# Sheet1.net
KiCad netlist of a schematic drawn in Altium Designer
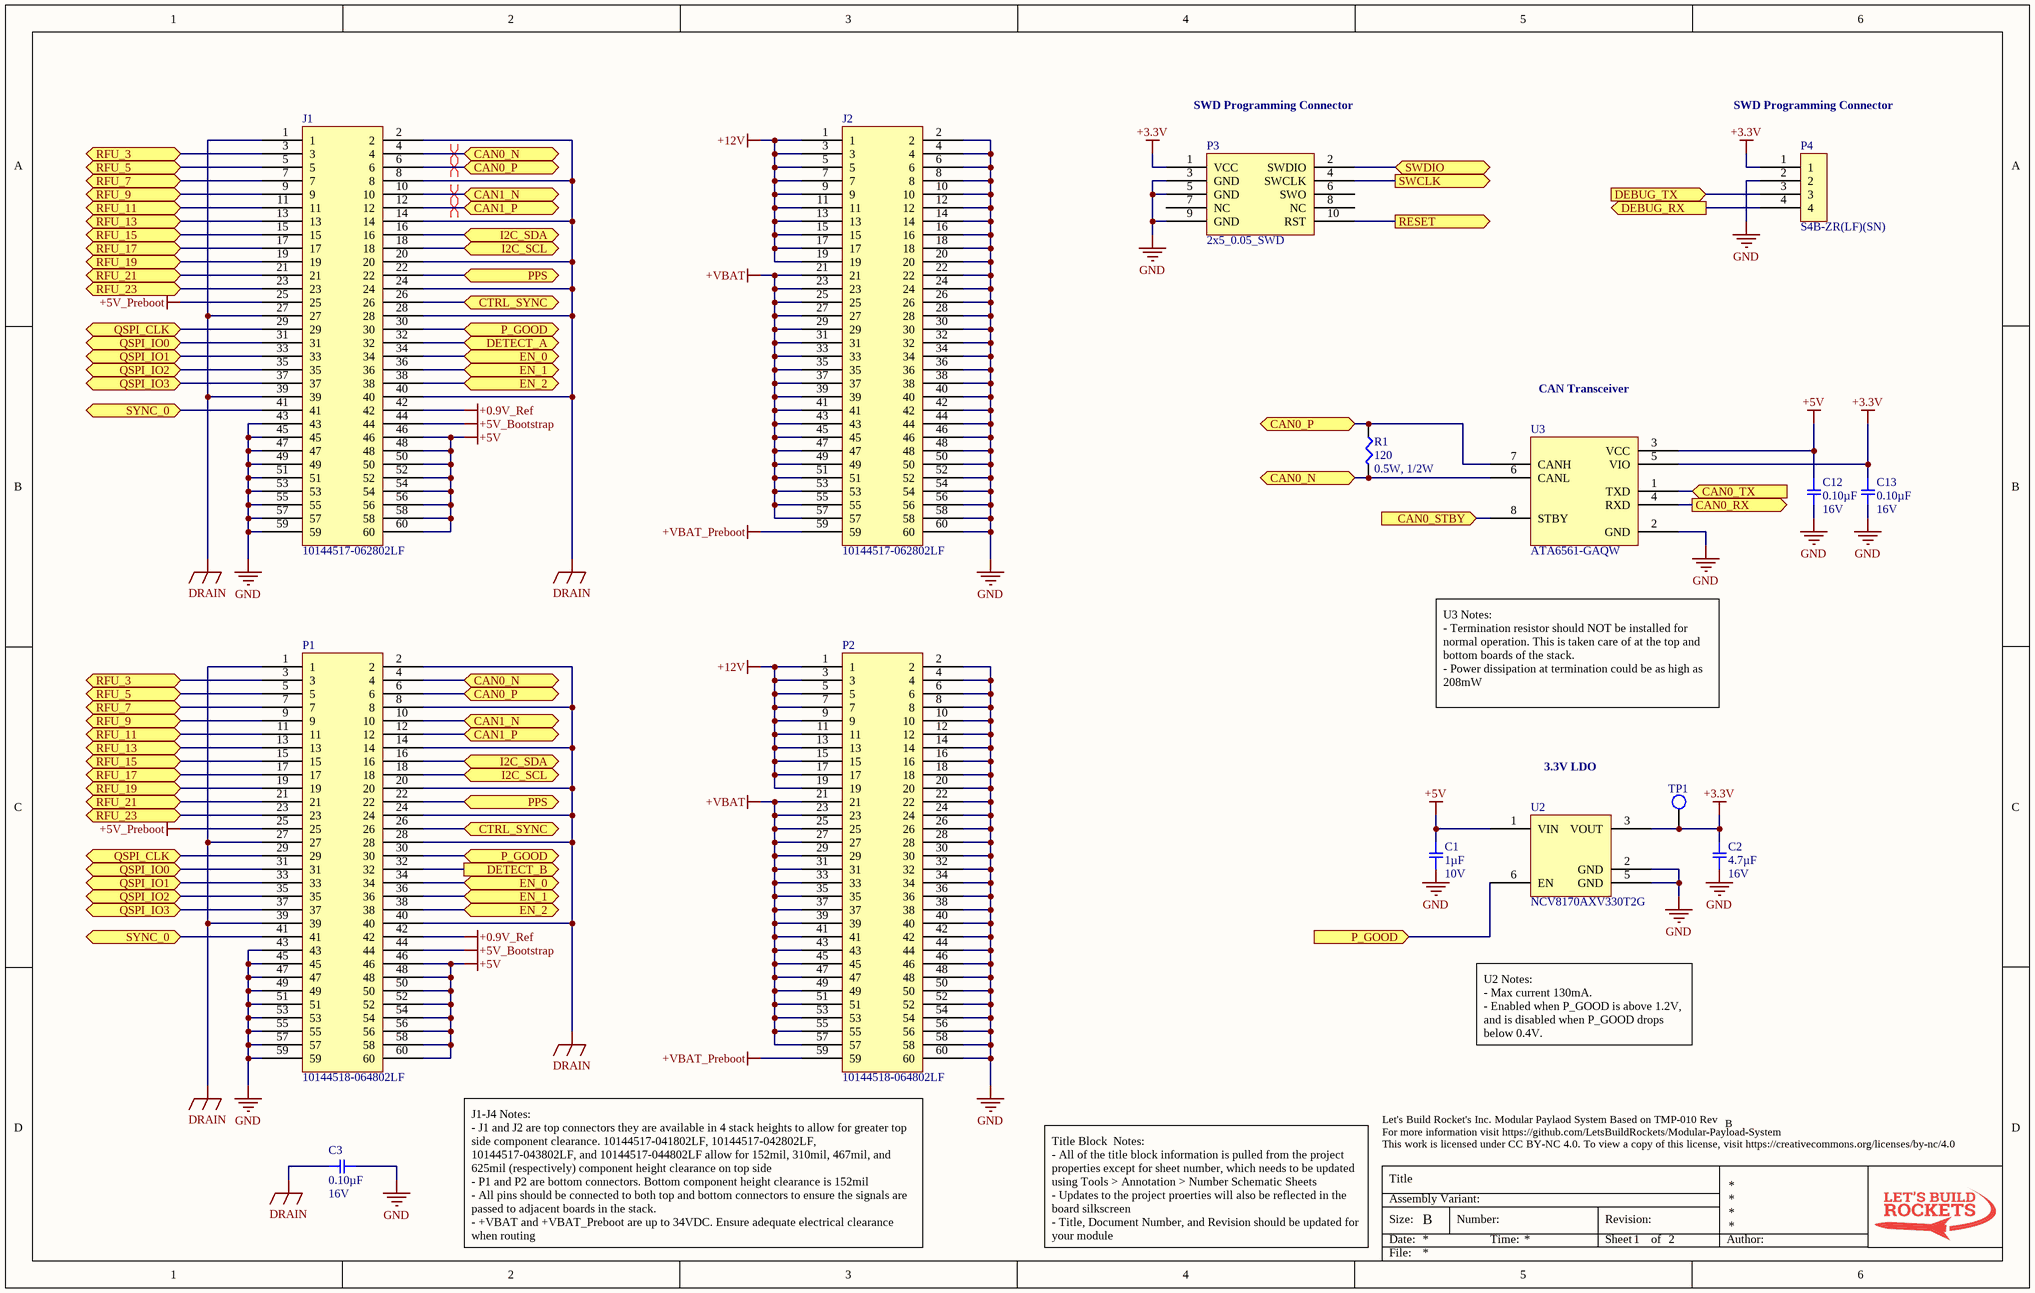
[diagram p0: Sheet1.SchDoc]

(export (version "E")
  (design (tool "Eeschema 10.0.6"))
  (components
    (comp (ref "C1")
      (value "1µF")
      (footprint "SMD-0402C")
      (description "CAP CER 1UF 10V X7S 0402")
      (fields
        (field (name "DIGI-KEY PART NUMBER") "490-13409-1-ND")
        (field (name "PART NUMBER") "GCM155C71A105KE38D")
        (field (name "VOLTAGE") "10V")
      )
      (libsource (lib "capacitor_murata_0402") (part "GCM155C71A105KE38D"))
    )
    (comp (ref "C2")
      (value "4.7µF")
      (footprint "SMD-0805C")
      (description "CAP CER 4.7UF 16V X7R 0805")
      (fields
        (field (name "DIGI-KEY PART NUMBER") "490-10557-1-ND")
        (field (name "PART NUMBER") "GCJ21BR71C475KA01L")
        (field (name "VOLTAGE") "16V")
      )
      (libsource (lib "capacitor_murata_0805") (part "GCJ21BR71C475KA01L"))
    )
    (comp (ref "C3")
      (value "0.10µF")
      (footprint "SMD-0402C")
      (description "CAP CER 0.1UF 16V X7R 0402")
      (fields
        (field (name "DIGI-KEY PART NUMBER") "490-4759-1-ND")
        (field (name "PART NUMBER") "GCM155R71C104KA55D")
        (field (name "VOLTAGE") "16V")
      )
      (libsource (lib "capacitor_murata_0402") (part "GCM155R71C104KA55D"))
    )
    (comp (ref "C12")
      (value "0.10µF")
      (footprint "SMD-0402C")
      (description "CAP CER 0.1UF 16V X7R 0402")
      (fields
        (field (name "DIGI-KEY PART NUMBER") "490-4759-1-ND")
        (field (name "PART NUMBER") "GCM155R71C104KA55D")
        (field (name "VOLTAGE") "16V")
      )
      (libsource (lib "capacitor_murata_0402") (part "GCM155R71C104KA55D"))
    )
    (comp (ref "C13")
      (value "0.10µF")
      (footprint "SMD-0402C")
      (description "CAP CER 0.1UF 16V X7R 0402")
      (fields
        (field (name "DIGI-KEY PART NUMBER") "490-4759-1-ND")
        (field (name "PART NUMBER") "GCM155R71C104KA55D")
        (field (name "VOLTAGE") "16V")
      )
      (libsource (lib "capacitor_murata_0402") (part "GCM155R71C104KA55D"))
    )
    (comp (ref "J1")
      (value "10144517-062802LF")
      (footprint "10144517-062802LF")
      (libsource (lib "ModularPayload") (part "10144517-062802LF"))
    )
    (comp (ref "J2")
      (value "10144517-062802LF")
      (footprint "10144517-062802LF")
      (libsource (lib "ModularPayload") (part "10144517-062802LF"))
    )
    (comp (ref "P1")
      (value "10144518-064802LF")
      (footprint "10144518-064802LF")
      (libsource (lib "ModularPayload") (part "10144518-064802LF"))
    )
    (comp (ref "P2")
      (value "10144518-064802LF")
      (footprint "10144518-064802LF")
      (libsource (lib "ModularPayload") (part "10144518-064802LF"))
    )
    (comp (ref "P3")
      (value "2x5_0.05_SWD")
      (footprint "2x5_0.05_R")
      (libsource (lib "ModularPayload") (part "2x5_0.05_SWD"))
    )
    (comp (ref "P4")
      (value "S4B-ZR(LF)(SN)")
      (footprint "S4B-ZR(LF)(SN)")
      (libsource (lib "ModularPayload") (part "S4B-ZR(LF)(SN)"))
    )
    (comp (ref "R1")
      (value "120")
      (footprint "SMD-0805-RES")
      (description "RES SMD 120 OHM 5% 1/2W 0805")
      (fields
        (field (name "PART NUMBER") "ERJ-P6WJ121V")
        (field (name "DIGI-KEY PART NUMBER") "P16943CT-ND")
        (field (name "POWER (WATTS)") "0.5W, 1/2W")
      )
      (libsource (lib "Panasonic_ERJ_0805") (part "ERJ-P6WJ121V"))
    )
    (comp (ref "TP1") (value "TP") (footprint "TP_SMD_40") (libsource (lib "TP") (part "TP")))
    (comp (ref "U2")
      (value "NCV8170AXV330T2G")
      (footprint "SOTFL50P160X60-6N")
      (libsource (lib "ModularPayload") (part "NCV8170AXV330T2G"))
    )
    (comp (ref "U3")
      (value "ATA6561-GAQW")
      (footprint "SOIC127P600X175-8N")
      (libsource (lib "ModularPayload") (part "ATA6561-GAQW"))
    )
  )
  (nets
    (net (code "1") (name "+0.9V_Ref") (class "Default")
      (node (ref "J1") (pin "42") (pinfunction "42_42") (pintype "passive"))
      (node (ref "P1") (pin "42") (pinfunction "42_42") (pintype "passive"))
    )
    (net (code "2") (name "+3.3V") (class "Default")
      (node (ref "C13") (pin "1") (pinfunction "1_1") (pintype "passive"))
      (node (ref "C2") (pin "2") (pinfunction "2_2") (pintype "passive"))
      (node (ref "P3") (pin "1") (pinfunction "VCC_1") (pintype "passive"))
      (node (ref "P4") (pin "1") (pinfunction "1_1") (pintype "passive"))
      (node (ref "TP1") (pin "1") (pintype "passive"))
      (node (ref "U2") (pin "3") (pinfunction "VOUT_3") (pintype "passive"))
      (node (ref "U3") (pin "5") (pinfunction "VIO_5") (pintype "passive"))
    )
    (net (code "3") (name "+5V") (class "Default")
      (node (ref "C1") (pin "2") (pinfunction "2_2") (pintype "passive"))
      (node (ref "C12") (pin "1") (pinfunction "1_1") (pintype "passive"))
      (node (ref "J1") (pin "46") (pinfunction "46_46") (pintype "passive"))
      (node (ref "J1") (pin "48") (pinfunction "48_48") (pintype "passive"))
      (node (ref "J1") (pin "50") (pinfunction "50_50") (pintype "passive"))
      (node (ref "J1") (pin "52") (pinfunction "52_52") (pintype "passive"))
      (node (ref "J1") (pin "54") (pinfunction "54_54") (pintype "passive"))
      (node (ref "J1") (pin "56") (pinfunction "56_56") (pintype "passive"))
      (node (ref "J1") (pin "58") (pinfunction "58_58") (pintype "passive"))
      (node (ref "J1") (pin "60") (pinfunction "60_60") (pintype "passive"))
      (node (ref "P1") (pin "46") (pinfunction "46_46") (pintype "passive"))
      (node (ref "P1") (pin "48") (pinfunction "48_48") (pintype "passive"))
      (node (ref "P1") (pin "50") (pinfunction "50_50") (pintype "passive"))
      (node (ref "P1") (pin "52") (pinfunction "52_52") (pintype "passive"))
      (node (ref "P1") (pin "54") (pinfunction "54_54") (pintype "passive"))
      (node (ref "P1") (pin "56") (pinfunction "56_56") (pintype "passive"))
      (node (ref "P1") (pin "58") (pinfunction "58_58") (pintype "passive"))
      (node (ref "P1") (pin "60") (pinfunction "60_60") (pintype "passive"))
      (node (ref "U2") (pin "1") (pinfunction "VIN_1") (pintype "passive"))
      (node (ref "U3") (pin "3") (pinfunction "VCC_3") (pintype "passive"))
    )
    (net (code "4") (name "+5V_Bootstrap") (class "Default")
      (node (ref "J1") (pin "44") (pinfunction "44_44") (pintype "passive"))
      (node (ref "P1") (pin "44") (pinfunction "44_44") (pintype "passive"))
    )
    (net (code "5") (name "+5V_Preboot") (class "Default")
      (node (ref "J1") (pin "25") (pinfunction "25_25") (pintype "passive"))
      (node (ref "P1") (pin "25") (pinfunction "25_25") (pintype "passive"))
    )
    (net (code "6") (name "+12V") (class "Default")
      (node (ref "J2") (pin "1") (pinfunction "1_1") (pintype "passive"))
      (node (ref "J2") (pin "11") (pinfunction "11_11") (pintype "passive"))
      (node (ref "J2") (pin "13") (pinfunction "13_13") (pintype "passive"))
      (node (ref "J2") (pin "15") (pinfunction "15_15") (pintype "passive"))
      (node (ref "J2") (pin "17") (pinfunction "17_17") (pintype "passive"))
      (node (ref "J2") (pin "19") (pinfunction "19_19") (pintype "passive"))
      (node (ref "J2") (pin "3") (pinfunction "3_3") (pintype "passive"))
      (node (ref "J2") (pin "5") (pinfunction "5_5") (pintype "passive"))
      (node (ref "J2") (pin "7") (pinfunction "7_7") (pintype "passive"))
      (node (ref "J2") (pin "9") (pinfunction "9_9") (pintype "passive"))
      (node (ref "P2") (pin "1") (pinfunction "1_1") (pintype "passive"))
      (node (ref "P2") (pin "11") (pinfunction "11_11") (pintype "passive"))
      (node (ref "P2") (pin "13") (pinfunction "13_13") (pintype "passive"))
      (node (ref "P2") (pin "15") (pinfunction "15_15") (pintype "passive"))
      (node (ref "P2") (pin "17") (pinfunction "17_17") (pintype "passive"))
      (node (ref "P2") (pin "19") (pinfunction "19_19") (pintype "passive"))
      (node (ref "P2") (pin "3") (pinfunction "3_3") (pintype "passive"))
      (node (ref "P2") (pin "5") (pinfunction "5_5") (pintype "passive"))
      (node (ref "P2") (pin "7") (pinfunction "7_7") (pintype "passive"))
      (node (ref "P2") (pin "9") (pinfunction "9_9") (pintype "passive"))
    )
    (net (code "7") (name "+VBAT") (class "Default")
      (node (ref "J2") (pin "21") (pinfunction "21_21") (pintype "passive"))
      (node (ref "J2") (pin "23") (pinfunction "23_23") (pintype "passive"))
      (node (ref "J2") (pin "25") (pinfunction "25_25") (pintype "passive"))
      (node (ref "J2") (pin "27") (pinfunction "27_27") (pintype "passive"))
      (node (ref "J2") (pin "29") (pinfunction "29_29") (pintype "passive"))
      (node (ref "J2") (pin "31") (pinfunction "31_31") (pintype "passive"))
      (node (ref "J2") (pin "33") (pinfunction "33_33") (pintype "passive"))
      (node (ref "J2") (pin "35") (pinfunction "35_35") (pintype "passive"))
      (node (ref "J2") (pin "37") (pinfunction "37_37") (pintype "passive"))
      (node (ref "J2") (pin "39") (pinfunction "39_39") (pintype "passive"))
      (node (ref "J2") (pin "41") (pinfunction "41_41") (pintype "passive"))
      (node (ref "J2") (pin "43") (pinfunction "43_43") (pintype "passive"))
      (node (ref "J2") (pin "45") (pinfunction "45_45") (pintype "passive"))
      (node (ref "J2") (pin "47") (pinfunction "47_47") (pintype "passive"))
      (node (ref "J2") (pin "49") (pinfunction "49_49") (pintype "passive"))
      (node (ref "J2") (pin "51") (pinfunction "51_51") (pintype "passive"))
      (node (ref "J2") (pin "53") (pinfunction "53_53") (pintype "passive"))
      (node (ref "J2") (pin "55") (pinfunction "55_55") (pintype "passive"))
      (node (ref "J2") (pin "57") (pinfunction "57_57") (pintype "passive"))
      (node (ref "P2") (pin "21") (pinfunction "21_21") (pintype "passive"))
      (node (ref "P2") (pin "23") (pinfunction "23_23") (pintype "passive"))
      (node (ref "P2") (pin "25") (pinfunction "25_25") (pintype "passive"))
      (node (ref "P2") (pin "27") (pinfunction "27_27") (pintype "passive"))
      (node (ref "P2") (pin "29") (pinfunction "29_29") (pintype "passive"))
      (node (ref "P2") (pin "31") (pinfunction "31_31") (pintype "passive"))
      (node (ref "P2") (pin "33") (pinfunction "33_33") (pintype "passive"))
      (node (ref "P2") (pin "35") (pinfunction "35_35") (pintype "passive"))
      (node (ref "P2") (pin "37") (pinfunction "37_37") (pintype "passive"))
      (node (ref "P2") (pin "39") (pinfunction "39_39") (pintype "passive"))
      (node (ref "P2") (pin "41") (pinfunction "41_41") (pintype "passive"))
      (node (ref "P2") (pin "43") (pinfunction "43_43") (pintype "passive"))
      (node (ref "P2") (pin "45") (pinfunction "45_45") (pintype "passive"))
      (node (ref "P2") (pin "47") (pinfunction "47_47") (pintype "passive"))
      (node (ref "P2") (pin "49") (pinfunction "49_49") (pintype "passive"))
      (node (ref "P2") (pin "51") (pinfunction "51_51") (pintype "passive"))
      (node (ref "P2") (pin "53") (pinfunction "53_53") (pintype "passive"))
      (node (ref "P2") (pin "55") (pinfunction "55_55") (pintype "passive"))
      (node (ref "P2") (pin "57") (pinfunction "57_57") (pintype "passive"))
    )
    (net (code "8") (name "+VBAT_Preboot") (class "Default")
      (node (ref "J2") (pin "59") (pinfunction "59_59") (pintype "passive"))
      (node (ref "P2") (pin "59") (pinfunction "59_59") (pintype "passive"))
    )
    (net (code "9") (name "/CAN0_N") (class "Default")
      (node (ref "J1") (pin "4") (pinfunction "4_4") (pintype "passive"))
      (node (ref "P1") (pin "4") (pinfunction "4_4") (pintype "passive"))
      (node (ref "R1") (pin "2") (pinfunction "2_2") (pintype "passive"))
      (node (ref "U3") (pin "6") (pinfunction "CANL_6") (pintype "passive"))
    )
    (net (code "10") (name "/CAN0_P") (class "Default")
      (node (ref "J1") (pin "6") (pinfunction "6_6") (pintype "passive"))
      (node (ref "P1") (pin "6") (pinfunction "6_6") (pintype "passive"))
      (node (ref "R1") (pin "1") (pinfunction "1_1") (pintype "passive"))
      (node (ref "U3") (pin "7") (pinfunction "CANH_7") (pintype "passive"))
    )
    (net (code "11") (name "/CAN0_RX") (class "Default")
      (node (ref "U3") (pin "4") (pinfunction "RXD_4") (pintype "passive"))
    )
    (net (code "12") (name "/CAN0_STBY") (class "Default")
      (node (ref "U3") (pin "8") (pinfunction "STBY_8") (pintype "passive"))
    )
    (net (code "13") (name "/CAN0_TX") (class "Default")
      (node (ref "U3") (pin "1") (pinfunction "TXD_1") (pintype "passive"))
    )
    (net (code "14") (name "/CAN1_N") (class "Default")
      (node (ref "J1") (pin "10") (pinfunction "10_10") (pintype "passive"))
      (node (ref "P1") (pin "10") (pinfunction "10_10") (pintype "passive"))
    )
    (net (code "15") (name "/CAN1_P") (class "Default")
      (node (ref "J1") (pin "12") (pinfunction "12_12") (pintype "passive"))
      (node (ref "P1") (pin "12") (pinfunction "12_12") (pintype "passive"))
    )
    (net (code "16") (name "/CTRL_SYNC") (class "Default")
      (node (ref "J1") (pin "26") (pinfunction "26_26") (pintype "passive"))
      (node (ref "P1") (pin "26") (pinfunction "26_26") (pintype "passive"))
    )
    (net (code "17") (name "/DEBUG_RX") (class "Default")
      (node (ref "P4") (pin "4") (pinfunction "4_4") (pintype "passive"))
    )
    (net (code "18") (name "/DEBUG_TX") (class "Default")
      (node (ref "P4") (pin "3") (pinfunction "3_3") (pintype "passive"))
    )
    (net (code "19") (name "/DETECT_A") (class "Default")
      (node (ref "J1") (pin "32") (pinfunction "32_32") (pintype "passive"))
    )
    (net (code "20") (name "/DETECT_B") (class "Default")
      (node (ref "P1") (pin "32") (pinfunction "32_32") (pintype "passive"))
    )
    (net (code "21") (name "/EN_0") (class "Default")
      (node (ref "J1") (pin "34") (pinfunction "34_34") (pintype "passive"))
      (node (ref "P1") (pin "34") (pinfunction "34_34") (pintype "passive"))
    )
    (net (code "22") (name "/EN_1") (class "Default")
      (node (ref "J1") (pin "36") (pinfunction "36_36") (pintype "passive"))
      (node (ref "P1") (pin "36") (pinfunction "36_36") (pintype "passive"))
    )
    (net (code "23") (name "/EN_2") (class "Default")
      (node (ref "J1") (pin "38") (pinfunction "38_38") (pintype "passive"))
      (node (ref "P1") (pin "38") (pinfunction "38_38") (pintype "passive"))
    )
    (net (code "24") (name "/I2C_SCL") (class "Default")
      (node (ref "J1") (pin "18") (pinfunction "18_18") (pintype "passive"))
      (node (ref "P1") (pin "18") (pinfunction "18_18") (pintype "passive"))
    )
    (net (code "25") (name "/I2C_SDA") (class "Default")
      (node (ref "J1") (pin "16") (pinfunction "16_16") (pintype "passive"))
      (node (ref "P1") (pin "16") (pinfunction "16_16") (pintype "passive"))
    )
    (net (code "26") (name "/PPS") (class "Default")
      (node (ref "J1") (pin "22") (pinfunction "22_22") (pintype "passive"))
      (node (ref "P1") (pin "22") (pinfunction "22_22") (pintype "passive"))
    )
    (net (code "27") (name "/P_GOOD") (class "Default")
      (node (ref "J1") (pin "30") (pinfunction "30_30") (pintype "passive"))
      (node (ref "P1") (pin "30") (pinfunction "30_30") (pintype "passive"))
      (node (ref "U2") (pin "6") (pinfunction "EN_6") (pintype "passive"))
    )
    (net (code "28") (name "/QSPI_CLK") (class "Default")
      (node (ref "J1") (pin "29") (pinfunction "29_29") (pintype "passive"))
      (node (ref "P1") (pin "29") (pinfunction "29_29") (pintype "passive"))
    )
    (net (code "29") (name "/QSPI_IO0") (class "Default")
      (node (ref "J1") (pin "31") (pinfunction "31_31") (pintype "passive"))
      (node (ref "P1") (pin "31") (pinfunction "31_31") (pintype "passive"))
    )
    (net (code "30") (name "/QSPI_IO1") (class "Default")
      (node (ref "J1") (pin "33") (pinfunction "33_33") (pintype "passive"))
      (node (ref "P1") (pin "33") (pinfunction "33_33") (pintype "passive"))
    )
    (net (code "31") (name "/QSPI_IO2") (class "Default")
      (node (ref "J1") (pin "35") (pinfunction "35_35") (pintype "passive"))
      (node (ref "P1") (pin "35") (pinfunction "35_35") (pintype "passive"))
    )
    (net (code "32") (name "/QSPI_IO3") (class "Default")
      (node (ref "J1") (pin "37") (pinfunction "37_37") (pintype "passive"))
      (node (ref "P1") (pin "37") (pinfunction "37_37") (pintype "passive"))
    )
    (net (code "33") (name "/RESET") (class "Default")
      (node (ref "P3") (pin "10") (pinfunction "RST_10") (pintype "passive"))
    )
    (net (code "34") (name "/RFU_3") (class "Default")
      (node (ref "J1") (pin "3") (pinfunction "3_3") (pintype "passive"))
      (node (ref "P1") (pin "3") (pinfunction "3_3") (pintype "passive"))
    )
    (net (code "35") (name "/RFU_5") (class "Default")
      (node (ref "J1") (pin "5") (pinfunction "5_5") (pintype "passive"))
      (node (ref "P1") (pin "5") (pinfunction "5_5") (pintype "passive"))
    )
    (net (code "36") (name "/RFU_7") (class "Default")
      (node (ref "J1") (pin "7") (pinfunction "7_7") (pintype "passive"))
      (node (ref "P1") (pin "7") (pinfunction "7_7") (pintype "passive"))
    )
    (net (code "37") (name "/RFU_9") (class "Default")
      (node (ref "J1") (pin "9") (pinfunction "9_9") (pintype "passive"))
      (node (ref "P1") (pin "9") (pinfunction "9_9") (pintype "passive"))
    )
    (net (code "38") (name "/RFU_11") (class "Default")
      (node (ref "J1") (pin "11") (pinfunction "11_11") (pintype "passive"))
      (node (ref "P1") (pin "11") (pinfunction "11_11") (pintype "passive"))
    )
    (net (code "39") (name "/RFU_13") (class "Default")
      (node (ref "J1") (pin "13") (pinfunction "13_13") (pintype "passive"))
      (node (ref "P1") (pin "13") (pinfunction "13_13") (pintype "passive"))
    )
    (net (code "40") (name "/RFU_15") (class "Default")
      (node (ref "J1") (pin "15") (pinfunction "15_15") (pintype "passive"))
      (node (ref "P1") (pin "15") (pinfunction "15_15") (pintype "passive"))
    )
    (net (code "41") (name "/RFU_17") (class "Default")
      (node (ref "J1") (pin "17") (pinfunction "17_17") (pintype "passive"))
      (node (ref "P1") (pin "17") (pinfunction "17_17") (pintype "passive"))
    )
    (net (code "42") (name "/RFU_19") (class "Default")
      (node (ref "J1") (pin "19") (pinfunction "19_19") (pintype "passive"))
      (node (ref "P1") (pin "19") (pinfunction "19_19") (pintype "passive"))
    )
    (net (code "43") (name "/RFU_21") (class "Default")
      (node (ref "J1") (pin "21") (pinfunction "21_21") (pintype "passive"))
      (node (ref "P1") (pin "21") (pinfunction "21_21") (pintype "passive"))
    )
    (net (code "44") (name "/RFU_23") (class "Default")
      (node (ref "J1") (pin "23") (pinfunction "23_23") (pintype "passive"))
      (node (ref "P1") (pin "23") (pinfunction "23_23") (pintype "passive"))
    )
    (net (code "45") (name "/SWCLK") (class "Default")
      (node (ref "P3") (pin "4") (pinfunction "SWCLK_4") (pintype "passive"))
    )
    (net (code "46") (name "/SWDIO") (class "Default")
      (node (ref "P3") (pin "2") (pinfunction "SWDIO_2") (pintype "passive"))
    )
    (net (code "47") (name "/SYNC_0") (class "Default")
      (node (ref "J1") (pin "41") (pinfunction "41_41") (pintype "passive"))
      (node (ref "P1") (pin "41") (pinfunction "41_41") (pintype "passive"))
    )
    (net (code "48") (name "DRAIN") (class "Default")
      (node (ref "C3") (pin "2") (pinfunction "2_2") (pintype "passive"))
      (node (ref "J1") (pin "1") (pinfunction "1_1") (pintype "passive"))
      (node (ref "J1") (pin "14") (pinfunction "14_14") (pintype "passive"))
      (node (ref "J1") (pin "2") (pinfunction "2_2") (pintype "passive"))
      (node (ref "J1") (pin "20") (pinfunction "20_20") (pintype "passive"))
      (node (ref "J1") (pin "24") (pinfunction "24_24") (pintype "passive"))
      (node (ref "J1") (pin "27") (pinfunction "27_27") (pintype "passive"))
      (node (ref "J1") (pin "28") (pinfunction "28_28") (pintype "passive"))
      (node (ref "J1") (pin "39") (pinfunction "39_39") (pintype "passive"))
      (node (ref "J1") (pin "40") (pinfunction "40_40") (pintype "passive"))
      (node (ref "J1") (pin "8") (pinfunction "8_8") (pintype "passive"))
      (node (ref "P1") (pin "1") (pinfunction "1_1") (pintype "passive"))
      (node (ref "P1") (pin "14") (pinfunction "14_14") (pintype "passive"))
      (node (ref "P1") (pin "2") (pinfunction "2_2") (pintype "passive"))
      (node (ref "P1") (pin "20") (pinfunction "20_20") (pintype "passive"))
      (node (ref "P1") (pin "24") (pinfunction "24_24") (pintype "passive"))
      (node (ref "P1") (pin "27") (pinfunction "27_27") (pintype "passive"))
      (node (ref "P1") (pin "28") (pinfunction "28_28") (pintype "passive"))
      (node (ref "P1") (pin "39") (pinfunction "39_39") (pintype "passive"))
      (node (ref "P1") (pin "40") (pinfunction "40_40") (pintype "passive"))
      (node (ref "P1") (pin "8") (pinfunction "8_8") (pintype "passive"))
    )
    (net (code "49") (name "GND") (class "Default")
      (node (ref "C1") (pin "1") (pinfunction "1_1") (pintype "passive"))
      (node (ref "C12") (pin "2") (pinfunction "2_2") (pintype "passive"))
      (node (ref "C13") (pin "2") (pinfunction "2_2") (pintype "passive"))
      (node (ref "C2") (pin "1") (pinfunction "1_1") (pintype "passive"))
      (node (ref "C3") (pin "1") (pinfunction "1_1") (pintype "passive"))
      (node (ref "J1") (pin "43") (pinfunction "43_43") (pintype "passive"))
      (node (ref "J1") (pin "45") (pinfunction "45_45") (pintype "passive"))
      (node (ref "J1") (pin "47") (pinfunction "47_47") (pintype "passive"))
      (node (ref "J1") (pin "49") (pinfunction "49_49") (pintype "passive"))
      (node (ref "J1") (pin "51") (pinfunction "51_51") (pintype "passive"))
      (node (ref "J1") (pin "53") (pinfunction "53_53") (pintype "passive"))
      (node (ref "J1") (pin "55") (pinfunction "55_55") (pintype "passive"))
      (node (ref "J1") (pin "57") (pinfunction "57_57") (pintype "passive"))
      (node (ref "J1") (pin "59") (pinfunction "59_59") (pintype "passive"))
      (node (ref "J2") (pin "10") (pinfunction "10_10") (pintype "passive"))
      (node (ref "J2") (pin "12") (pinfunction "12_12") (pintype "passive"))
      (node (ref "J2") (pin "14") (pinfunction "14_14") (pintype "passive"))
      (node (ref "J2") (pin "16") (pinfunction "16_16") (pintype "passive"))
      (node (ref "J2") (pin "18") (pinfunction "18_18") (pintype "passive"))
      (node (ref "J2") (pin "2") (pinfunction "2_2") (pintype "passive"))
      (node (ref "J2") (pin "20") (pinfunction "20_20") (pintype "passive"))
      (node (ref "J2") (pin "22") (pinfunction "22_22") (pintype "passive"))
      (node (ref "J2") (pin "24") (pinfunction "24_24") (pintype "passive"))
      (node (ref "J2") (pin "26") (pinfunction "26_26") (pintype "passive"))
      (node (ref "J2") (pin "28") (pinfunction "28_28") (pintype "passive"))
      (node (ref "J2") (pin "30") (pinfunction "30_30") (pintype "passive"))
      (node (ref "J2") (pin "32") (pinfunction "32_32") (pintype "passive"))
      (node (ref "J2") (pin "34") (pinfunction "34_34") (pintype "passive"))
      (node (ref "J2") (pin "36") (pinfunction "36_36") (pintype "passive"))
      (node (ref "J2") (pin "38") (pinfunction "38_38") (pintype "passive"))
      (node (ref "J2") (pin "4") (pinfunction "4_4") (pintype "passive"))
      (node (ref "J2") (pin "40") (pinfunction "40_40") (pintype "passive"))
      (node (ref "J2") (pin "42") (pinfunction "42_42") (pintype "passive"))
      (node (ref "J2") (pin "44") (pinfunction "44_44") (pintype "passive"))
      (node (ref "J2") (pin "46") (pinfunction "46_46") (pintype "passive"))
      (node (ref "J2") (pin "48") (pinfunction "48_48") (pintype "passive"))
      (node (ref "J2") (pin "50") (pinfunction "50_50") (pintype "passive"))
      (node (ref "J2") (pin "52") (pinfunction "52_52") (pintype "passive"))
      (node (ref "J2") (pin "54") (pinfunction "54_54") (pintype "passive"))
      (node (ref "J2") (pin "56") (pinfunction "56_56") (pintype "passive"))
      (node (ref "J2") (pin "58") (pinfunction "58_58") (pintype "passive"))
      (node (ref "J2") (pin "6") (pinfunction "6_6") (pintype "passive"))
      (node (ref "J2") (pin "60") (pinfunction "60_60") (pintype "passive"))
      (node (ref "J2") (pin "8") (pinfunction "8_8") (pintype "passive"))
      (node (ref "P1") (pin "43") (pinfunction "43_43") (pintype "passive"))
      (node (ref "P1") (pin "45") (pinfunction "45_45") (pintype "passive"))
      (node (ref "P1") (pin "47") (pinfunction "47_47") (pintype "passive"))
      (node (ref "P1") (pin "49") (pinfunction "49_49") (pintype "passive"))
      (node (ref "P1") (pin "51") (pinfunction "51_51") (pintype "passive"))
      (node (ref "P1") (pin "53") (pinfunction "53_53") (pintype "passive"))
      (node (ref "P1") (pin "55") (pinfunction "55_55") (pintype "passive"))
      (node (ref "P1") (pin "57") (pinfunction "57_57") (pintype "passive"))
      (node (ref "P1") (pin "59") (pinfunction "59_59") (pintype "passive"))
      (node (ref "P2") (pin "10") (pinfunction "10_10") (pintype "passive"))
      (node (ref "P2") (pin "12") (pinfunction "12_12") (pintype "passive"))
      (node (ref "P2") (pin "14") (pinfunction "14_14") (pintype "passive"))
      (node (ref "P2") (pin "16") (pinfunction "16_16") (pintype "passive"))
      (node (ref "P2") (pin "18") (pinfunction "18_18") (pintype "passive"))
      (node (ref "P2") (pin "2") (pinfunction "2_2") (pintype "passive"))
      (node (ref "P2") (pin "20") (pinfunction "20_20") (pintype "passive"))
      (node (ref "P2") (pin "22") (pinfunction "22_22") (pintype "passive"))
      (node (ref "P2") (pin "24") (pinfunction "24_24") (pintype "passive"))
      (node (ref "P2") (pin "26") (pinfunction "26_26") (pintype "passive"))
      (node (ref "P2") (pin "28") (pinfunction "28_28") (pintype "passive"))
      (node (ref "P2") (pin "30") (pinfunction "30_30") (pintype "passive"))
      (node (ref "P2") (pin "32") (pinfunction "32_32") (pintype "passive"))
      (node (ref "P2") (pin "34") (pinfunction "34_34") (pintype "passive"))
      (node (ref "P2") (pin "36") (pinfunction "36_36") (pintype "passive"))
      (node (ref "P2") (pin "38") (pinfunction "38_38") (pintype "passive"))
      (node (ref "P2") (pin "4") (pinfunction "4_4") (pintype "passive"))
      (node (ref "P2") (pin "40") (pinfunction "40_40") (pintype "passive"))
      (node (ref "P2") (pin "42") (pinfunction "42_42") (pintype "passive"))
      (node (ref "P2") (pin "44") (pinfunction "44_44") (pintype "passive"))
      (node (ref "P2") (pin "46") (pinfunction "46_46") (pintype "passive"))
      (node (ref "P2") (pin "48") (pinfunction "48_48") (pintype "passive"))
      (node (ref "P2") (pin "50") (pinfunction "50_50") (pintype "passive"))
      (node (ref "P2") (pin "52") (pinfunction "52_52") (pintype "passive"))
      (node (ref "P2") (pin "54") (pinfunction "54_54") (pintype "passive"))
      (node (ref "P2") (pin "56") (pinfunction "56_56") (pintype "passive"))
      (node (ref "P2") (pin "58") (pinfunction "58_58") (pintype "passive"))
      (node (ref "P2") (pin "6") (pinfunction "6_6") (pintype "passive"))
      (node (ref "P2") (pin "60") (pinfunction "60_60") (pintype "passive"))
      (node (ref "P2") (pin "8") (pinfunction "8_8") (pintype "passive"))
      (node (ref "P3") (pin "3") (pinfunction "GND_3") (pintype "passive"))
      (node (ref "P3") (pin "5") (pinfunction "GND_5") (pintype "passive"))
      (node (ref "P3") (pin "9") (pinfunction "GND_9") (pintype "passive"))
      (node (ref "P4") (pin "2") (pinfunction "2_2") (pintype "passive"))
      (node (ref "U2") (pin "2") (pinfunction "GND_2") (pintype "passive"))
      (node (ref "U2") (pin "5") (pinfunction "GND_5") (pintype "passive"))
      (node (ref "U3") (pin "2") (pinfunction "GND_2") (pintype "passive"))
    )
    (net (code "50") (name "unconnected-(P3-NC-Pad7)") (class "Default")
      (node (ref "P3") (pin "7") (pinfunction "NC_7") (pintype "passive"))
    )
    (net (code "51") (name "unconnected-(P3-NC-Pad8)") (class "Default")
      (node (ref "P3") (pin "8") (pinfunction "NC_8") (pintype "passive"))
    )
    (net (code "52") (name "unconnected-(P3-SWO-Pad6)") (class "Default")
      (node (ref "P3") (pin "6") (pinfunction "SWO_6") (pintype "passive"))
    )
  )
)
